# Power.net
KiCad netlist of a schematic drawn in Altium Designer
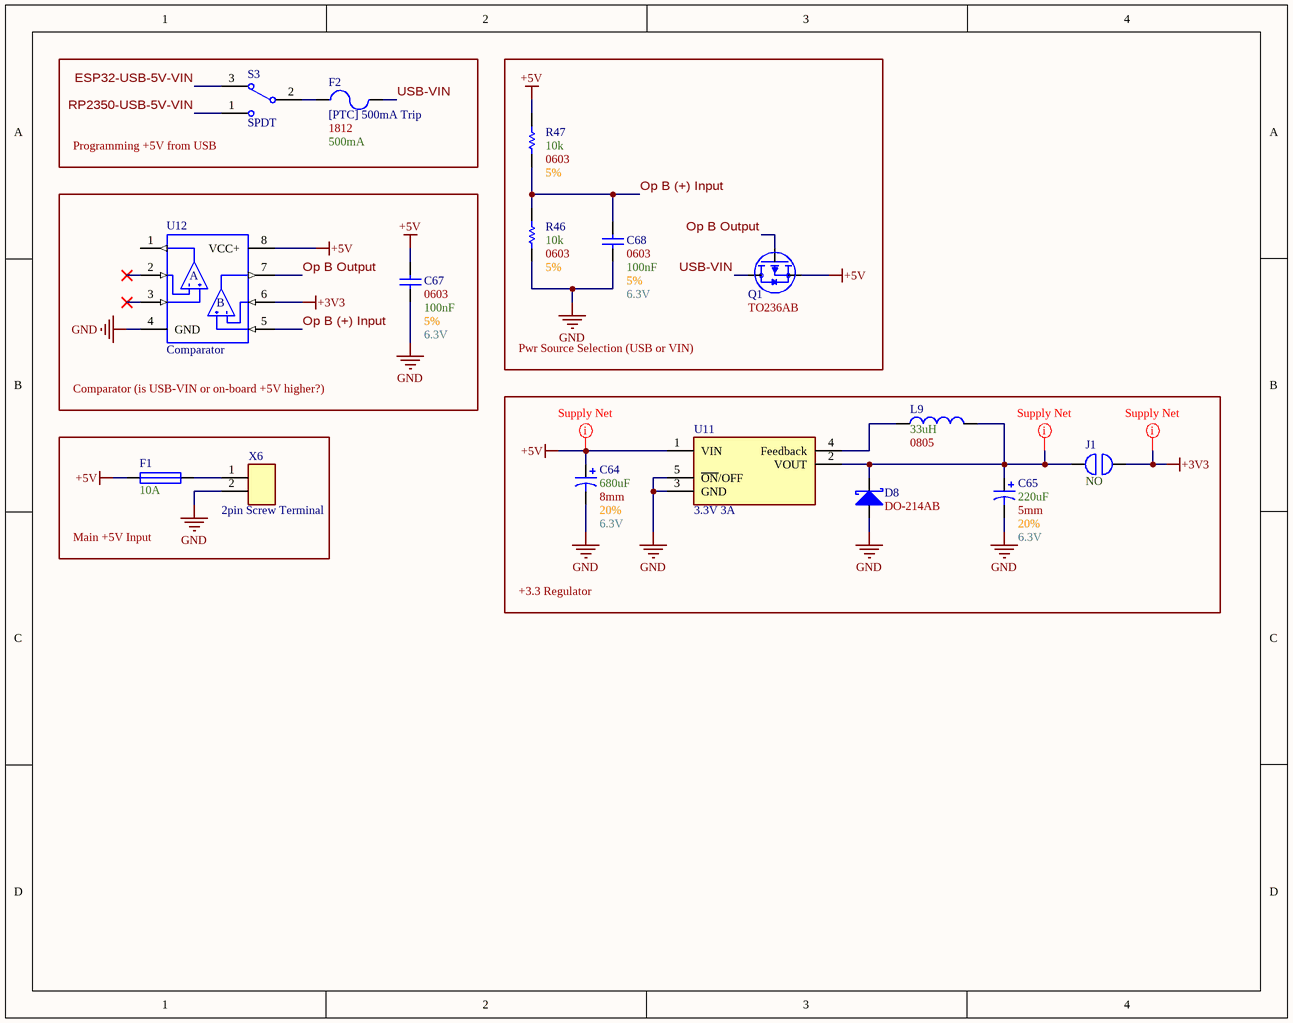
[diagram p0: Power.SchDoc]

(export (version "E")
  (design (tool "Eeschema 10.0.6"))
  (components
    (comp (ref "C64")
      (value "SMD Polarized")
      (footprint "[Cap] SMD Polarized, 8mm")
      (fields
        (field (name "TOLERANCE") "20%")
        (field (name "MAX VOLTAGE") "6.3V")
        (field (name "CAPACITANCE") "680uF")
        (field (name "DIAMETER") "8mm")
      )
      (libsource (lib "RADM Components") (part "[Cap] SMD Polarized"))
    )
    (comp (ref "C65")
      (value "SMD Polarized")
      (footprint "[Cap] SMD Polarized, 5mm")
      (fields
        (field (name "TOLERANCE") "20%")
        (field (name "MAX VOLTAGE") "6.3V")
        (field (name "CAPACITANCE") "220uF")
        (field (name "DIAMETER") "5mm")
      )
      (libsource (lib "RADM Components") (part "[Cap] SMD Polarized"))
    )
    (comp (ref "C67")
      (value "[Cap] SMD Nonpolarized")
      (footprint "[Cap] SMD 0603")
      (fields
        (field (name "SIZE PACKAGE") "0603")
        (field (name "CAPACITANCE") "100nF")
        (field (name "VOLTAGE") "6.3V")
        (field (name "TOLERANCE") "5%")
      )
      (libsource (lib "RADM Components") (part "[Cap] SMD Nonpolarized"))
    )
    (comp (ref "C68")
      (value "[Cap] SMD Nonpolarized")
      (footprint "[Cap] SMD 0603")
      (fields
        (field (name "SIZE PACKAGE") "0603")
        (field (name "CAPACITANCE") "100nF")
        (field (name "VOLTAGE") "6.3V")
        (field (name "TOLERANCE") "5%")
      )
      (libsource (lib "RADM Components") (part "[Cap] SMD Nonpolarized"))
    )
    (comp (ref "D8")
      (value "Schottky")
      (footprint "[Diode] SMD DO-214AB")
      (description "Generic")
      (fields (field (name "SIZE PACKAGE") "DO-214AB"))
      (libsource (lib "RADM Components") (part "[Diode] SMD Schottky"))
    )
    (comp (ref "F1")
      (value "Right-Angle")
      (footprint "[Fuse] Blade Right-Angle")
      (fields (field (name "AMPERAGE") "10A"))
      (libsource (lib "RADM Components") (part "[Fuse] Blade Right-Angle"))
    )
    (comp (ref "F2")
      (value "[PTC] 500mA Trip")
      (footprint "[PTC] 500mA Trip")
      (description "MF-MSMF050-2")
      (fields (field (name "SIZE PACKAGE") "1812") (field (name "TRIP CURRENT") "500mA"))
      (libsource (lib "RADM Components") (part "[PTC] 500mA Trip"))
    )
    (comp (ref "J1")
      (value "[Jump] SMD Jumper")
      (footprint "[Jumper] Solderable Jumper")
      (description "Solderable jumper")
      (fields (field (name "NO/NC") "NO"))
      (libsource (lib "RADM Components") (part "[Jump] SMD Jumper"))
    )
    (comp (ref "L9")
      (value "SMD Inductor")
      (footprint "[Inductor] SMD 0805")
      (fields (field (name "SIZE PACKAGE") "0805") (field (name "INDUCTANCE") "33uH"))
      (libsource (lib "RADM Components") (part "[Inductor] SMD Inductor"))
    )
    (comp (ref "Q1")
      (value "PMV48XP")
      (footprint "[FET] P-Channel Mosfet")
      (fields (field (name "SIZE PACKAGE") "TO236AB"))
      (libsource (lib "RADM Components") (part "[FET] P-Channel MOSFET"))
    )
    (comp (ref "R46")
      (value "[Res] SMD Resistor")
      (footprint "[Res] SMD 0603")
      (description "Generic")
      (fields
        (field (name "RESISTANCE") "10k")
        (field (name "SIZE PACKAGE") "0603")
        (field (name "TOLERANCE") "5%")
      )
      (libsource (lib "RADM Components") (part "[Res] SMD Resistor"))
    )
    (comp (ref "R47")
      (value "[Res] SMD Resistor")
      (footprint "[Res] SMD 0603")
      (description "Generic")
      (fields
        (field (name "RESISTANCE") "10k")
        (field (name "SIZE PACKAGE") "0603")
        (field (name "TOLERANCE") "5%")
      )
      (libsource (lib "RADM Components") (part "[Res] SMD Resistor"))
    )
    (comp (ref "S3")
      (value "SPDT")
      (footprint "[Switch] SPDT")
      (libsource (lib "RADM Components") (part "[Switch] SPDT Switch"))
    )
    (comp (ref "U11")
      (value "3.3V 3A")
      (footprint "[Reg] 3V3 Regulator (4)")
      (description "3A")
      (libsource (lib "RADM Components") (part "[Reg] 3V3 Regulator (4)"))
    )
    (comp (ref "U12")
      (value "Comparator")
      (footprint "[IC] Dual Op-Ap")
      (description "LMV358IDGKR")
      (libsource (lib "RADM Components") (part "[IC] Dual Op-Amp"))
    )
    (comp (ref "X6")
      (value "2pin Screw Terminal")
      (footprint "[Screw Terminal] 2pin 5mm")
      (libsource (lib "RADM Connectors") (part "[Screw Terminal] 2pin"))
    )
  )
  (nets
    (net (code "1") (name "+3V3") (class "Default")
      (node (ref "J1") (pin "2") (pintype "passive"))
      (node (ref "U12") (pin "6") (pinfunction "2IN-_6") (pintype "input"))
    )
    (net (code "2") (name "+5V") (class "Default")
      (node (ref "C64") (pin "1") (pinfunction "1_1") (pintype "passive"))
      (node (ref "C67") (pin "2") (pinfunction "2_2") (pintype "passive"))
      (node (ref "F1") (pin "1") (pinfunction "1_1") (pintype "passive"))
      (node (ref "Q1") (pin "2") (pinfunction "S_2") (pintype "passive"))
      (node (ref "R47") (pin "2") (pinfunction "2_2") (pintype "passive"))
      (node (ref "U11") (pin "1") (pinfunction "VIN_1") (pintype "passive"))
      (node (ref "U12") (pin "8") (pinfunction "VCC+_8") (pintype "power_in"))
    )
    (net (code "3") (name "/ESP32-USB-5V-VIN") (class "Default")
      (node (ref "S3") (pin "3") (pinfunction "3_3") (pintype "passive"))
    )
    (net (code "4") (name "/Op B (+) Input") (class "Default")
      (node (ref "C68") (pin "2") (pinfunction "2_2") (pintype "passive"))
      (node (ref "R46") (pin "2") (pinfunction "2_2") (pintype "passive"))
      (node (ref "R47") (pin "1") (pinfunction "1_1") (pintype "passive"))
      (node (ref "U12") (pin "5") (pinfunction "2IN+_5") (pintype "input"))
    )
    (net (code "5") (name "/Op B Output") (class "Default")
      (node (ref "Q1") (pin "1") (pinfunction "G_1") (pintype "passive"))
      (node (ref "U12") (pin "7") (pinfunction "2OUT_7") (pintype "output"))
    )
    (net (code "6") (name "/RP2350-USB-5V-VIN") (class "Default")
      (node (ref "S3") (pin "1") (pinfunction "1_1") (pintype "passive"))
    )
    (net (code "7") (name "/USB-VIN") (class "Default")
      (node (ref "F2") (pin "2") (pinfunction "2_2") (pintype "passive"))
      (node (ref "Q1") (pin "3") (pinfunction "D_3") (pintype "passive"))
    )
    (net (code "8") (name "GND") (class "Default")
      (node (ref "C64") (pin "2") (pinfunction "2_2") (pintype "passive"))
      (node (ref "C65") (pin "2") (pinfunction "2_2") (pintype "passive"))
      (node (ref "C67") (pin "1") (pinfunction "1_1") (pintype "passive"))
      (node (ref "C68") (pin "1") (pinfunction "1_1") (pintype "passive"))
      (node (ref "D8") (pin "2") (pinfunction "A_2") (pintype "power_in"))
      (node (ref "R46") (pin "1") (pinfunction "1_1") (pintype "passive"))
      (node (ref "U11") (pin "3") (pinfunction "GND_3") (pintype "passive"))
      (node (ref "U11") (pin "5") (pinfunction "~{ON}/OFF_5") (pintype "passive"))
      (node (ref "U12") (pin "4") (pinfunction "GND_4") (pintype "power_in"))
      (node (ref "X6") (pin "2") (pintype "power_in"))
    )
    (net (code "9") (name "Net-(D8-K)") (class "Default")
      (node (ref "C65") (pin "1") (pinfunction "1_1") (pintype "passive"))
      (node (ref "D8") (pin "1") (pinfunction "K_1") (pintype "power_in"))
      (node (ref "J1") (pin "1") (pintype "passive"))
      (node (ref "L9") (pin "2") (pinfunction "2_2") (pintype "passive"))
      (node (ref "U11") (pin "2") (pinfunction "VOUT_2") (pintype "passive"))
    )
    (net (code "10") (name "Net-(F1-Pad2)") (class "Default")
      (node (ref "F1") (pin "2") (pinfunction "2_2") (pintype "passive"))
      (node (ref "X6") (pin "1") (pintype "power_in"))
    )
    (net (code "11") (name "Net-(F2-Pad1)") (class "Default")
      (node (ref "F2") (pin "1") (pinfunction "1_1") (pintype "passive"))
      (node (ref "S3") (pin "2") (pinfunction "2_2") (pintype "passive"))
    )
    (net (code "12") (name "Net-(U11-Feedback)") (class "Default")
      (node (ref "L9") (pin "1") (pinfunction "1_1") (pintype "passive"))
      (node (ref "U11") (pin "4") (pinfunction "Feedback_4") (pintype "passive"))
    )
    (net (code "13") (name "unconnected-(U12-1IN+-Pad3)") (class "Default")
      (node (ref "U12") (pin "3") (pinfunction "1IN+_3") (pintype "input+no_connect"))
    )
    (net (code "14") (name "unconnected-(U12-1IN--Pad2)") (class "Default")
      (node (ref "U12") (pin "2") (pinfunction "1IN-_2") (pintype "input+no_connect"))
    )
    (net (code "15") (name "unconnected-(U12-1OUT-Pad1)") (class "Default")
      (node (ref "U12") (pin "1") (pinfunction "1OUT_1") (pintype "output"))
    )
  )
)
